# 03_-_MCU.net
KiCad netlist of a schematic drawn in Altium Designer
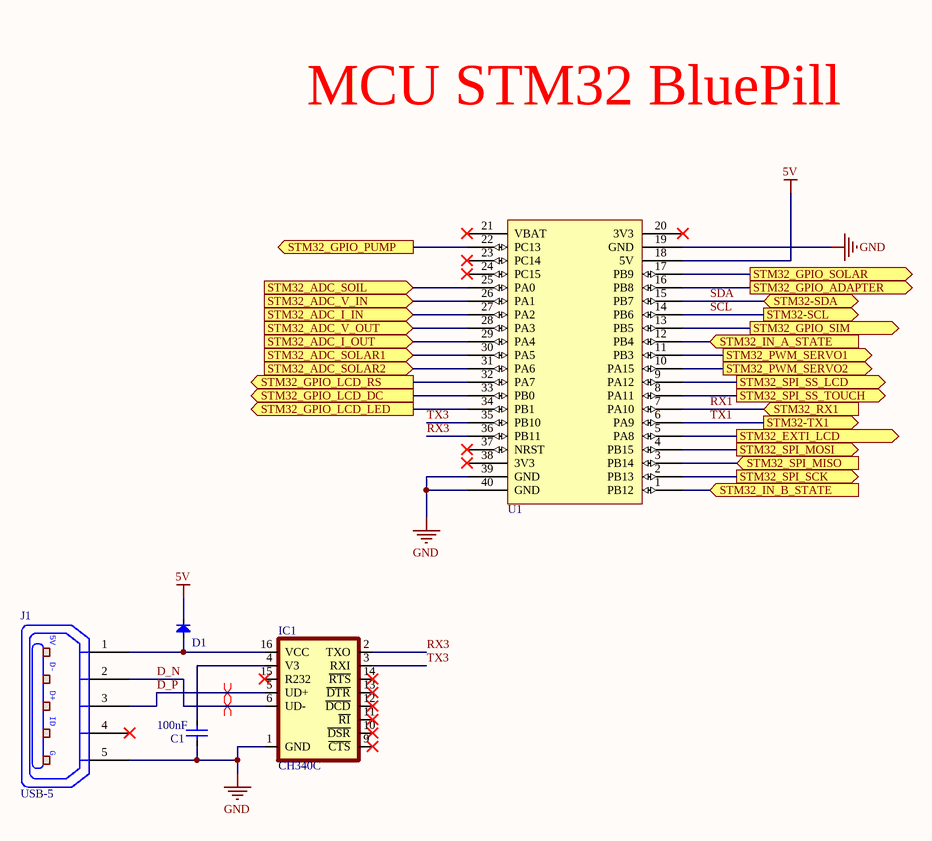
[diagram p0: [03] - MCU.SchDoc]

(export (version "E")
  (design (tool "Eeschema 10.0.6"))
  (components
    (comp (ref "C1")
      (value "100nF")
      (footprint "CAP_0805")
      (description "Capacitor")
      (fields (field (name "PUBLISHER") "Altium Limited"))
      (libsource (lib "My Library") (part "CapSMD"))
    )
    (comp (ref "D1")
      (value "SS34")
      (footprint "DO-214AC(SMA)")
      (description "Diode Schottky 1N5822 3A 40V SMA")
      (fields (field (name "PUBLISHER") "Altium Limited"))
      (libsource (lib "My Library") (part "Diode SMD"))
    )
    (comp (ref "IC1")
      (value "CH340C")
      (footprint "SO016")
      (description "USB to serial chip CH340")
      (fields (field (name "MF") "WCH"))
      (libsource (lib "My Library") (part "CH340C"))
    )
    (comp (ref "J1")
      (value "USB-5")
      (footprint "USB-M1")
      (fields
        (field (name "MANUFACTURER") "FCI")
        (field (name "MANUFACTURER PART NUMBER") "10118193-0001LF")
        (field (name ".CREATOR") "MM")
        (field (name ".CHECKED PCB") "RF")
        (field (name ".CHECKED SCH") "MM")
      )
      (libsource (lib "My Library") (part "USB-5"))
    )
    (comp (ref "U1")
      (value "STM32 BluePill")
      (footprint "STM32 Bluepill")
      (libsource (lib "My Library") (part "STM32 BluePill"))
    )
  )
  (nets
    (net (code "1") (name "/D_N") (class "Default")
      (node (ref "IC1") (pin "6") (pinfunction "UD-_6") (pintype "bidirectional"))
      (node (ref "J1") (pin "2") (pinfunction "P2_2") (pintype "passive"))
    )
    (net (code "2") (name "/D_P") (class "Default")
      (node (ref "IC1") (pin "5") (pinfunction "UD+_5") (pintype "bidirectional"))
      (node (ref "J1") (pin "3") (pinfunction "P3_3") (pintype "passive"))
    )
    (net (code "3") (name "/RX1") (class "Default")
      (node (ref "U1") (pin "7") (pinfunction "PA10_7") (pintype "bidirectional"))
    )
    (net (code "4") (name "/RX3") (class "Default")
      (node (ref "IC1") (pin "2") (pinfunction "TXO_2") (pintype "bidirectional"))
      (node (ref "U1") (pin "36") (pinfunction "PB11_36") (pintype "bidirectional"))
    )
    (net (code "5") (name "/SCL") (class "Default")
      (node (ref "U1") (pin "14") (pinfunction "PB6_14") (pintype "bidirectional"))
    )
    (net (code "6") (name "/SDA") (class "Default")
      (node (ref "U1") (pin "15") (pinfunction "PB7_15") (pintype "bidirectional"))
    )
    (net (code "7") (name "/STM32_ADC_I_IN") (class "Default")
      (node (ref "U1") (pin "27") (pinfunction "PA2_27") (pintype "bidirectional"))
    )
    (net (code "8") (name "/STM32_ADC_I_OUT") (class "Default")
      (node (ref "U1") (pin "29") (pinfunction "PA4_29") (pintype "bidirectional"))
    )
    (net (code "9") (name "/STM32_ADC_SOIL") (class "Default")
      (node (ref "U1") (pin "25") (pinfunction "PA0_25") (pintype "bidirectional"))
    )
    (net (code "10") (name "/STM32_ADC_SOLAR1") (class "Default")
      (node (ref "U1") (pin "30") (pinfunction "PA5_30") (pintype "bidirectional"))
    )
    (net (code "11") (name "/STM32_ADC_SOLAR2") (class "Default")
      (node (ref "U1") (pin "31") (pinfunction "PA6_31") (pintype "bidirectional"))
    )
    (net (code "12") (name "/STM32_ADC_V_IN") (class "Default")
      (node (ref "U1") (pin "26") (pinfunction "PA1_26") (pintype "bidirectional"))
    )
    (net (code "13") (name "/STM32_ADC_V_OUT") (class "Default")
      (node (ref "U1") (pin "28") (pinfunction "PA3_28") (pintype "bidirectional"))
    )
    (net (code "14") (name "/STM32_EXTI_LCD") (class "Default")
      (node (ref "U1") (pin "5") (pinfunction "PA8_5") (pintype "bidirectional"))
    )
    (net (code "15") (name "/STM32_GPIO_ADAPTER") (class "Default")
      (node (ref "U1") (pin "16") (pinfunction "PB8_16") (pintype "bidirectional"))
    )
    (net (code "16") (name "/STM32_GPIO_LCD_DC") (class "Default")
      (node (ref "U1") (pin "33") (pinfunction "PB0_33") (pintype "bidirectional"))
    )
    (net (code "17") (name "/STM32_GPIO_LCD_LED") (class "Default")
      (node (ref "U1") (pin "34") (pinfunction "PB1_34") (pintype "bidirectional"))
    )
    (net (code "18") (name "/STM32_GPIO_LCD_RS") (class "Default")
      (node (ref "U1") (pin "32") (pinfunction "PA7_32") (pintype "bidirectional"))
    )
    (net (code "19") (name "/STM32_GPIO_PUMP") (class "Default")
      (node (ref "U1") (pin "22") (pinfunction "PC13_22") (pintype "bidirectional"))
    )
    (net (code "20") (name "/STM32_GPIO_SIM") (class "Default")
      (node (ref "U1") (pin "13") (pinfunction "PB5_13") (pintype "bidirectional"))
    )
    (net (code "21") (name "/STM32_GPIO_SOLAR") (class "Default")
      (node (ref "U1") (pin "17") (pinfunction "PB9_17") (pintype "bidirectional"))
    )
    (net (code "22") (name "/STM32_IN_A_STATE") (class "Default")
      (node (ref "U1") (pin "12") (pinfunction "PB4_12") (pintype "bidirectional"))
    )
    (net (code "23") (name "/STM32_IN_B_STATE") (class "Default")
      (node (ref "U1") (pin "1") (pinfunction "PB12_1") (pintype "bidirectional"))
    )
    (net (code "24") (name "/STM32_PWM_SERVO1") (class "Default")
      (node (ref "U1") (pin "11") (pinfunction "PB3_11") (pintype "bidirectional"))
    )
    (net (code "25") (name "/STM32_PWM_SERVO2") (class "Default")
      (node (ref "U1") (pin "10") (pinfunction "PA15_10") (pintype "bidirectional"))
    )
    (net (code "26") (name "/STM32_SPI_MISO") (class "Default")
      (node (ref "U1") (pin "3") (pinfunction "PB14_3") (pintype "bidirectional"))
    )
    (net (code "27") (name "/STM32_SPI_MOSI") (class "Default")
      (node (ref "U1") (pin "4") (pinfunction "PB15_4") (pintype "bidirectional"))
    )
    (net (code "28") (name "/STM32_SPI_SCK") (class "Default")
      (node (ref "U1") (pin "2") (pinfunction "PB13_2") (pintype "bidirectional"))
    )
    (net (code "29") (name "/STM32_SPI_SS_LCD") (class "Default")
      (node (ref "U1") (pin "9") (pinfunction "PA12_9") (pintype "bidirectional"))
    )
    (net (code "30") (name "/STM32_SPI_SS_TOUCH") (class "Default")
      (node (ref "U1") (pin "8") (pinfunction "PA11_8") (pintype "bidirectional"))
    )
    (net (code "31") (name "/TX1") (class "Default")
      (node (ref "U1") (pin "6") (pinfunction "PA9_6") (pintype "bidirectional"))
    )
    (net (code "32") (name "/TX3") (class "Default")
      (node (ref "IC1") (pin "3") (pinfunction "RXI_3") (pintype "bidirectional"))
      (node (ref "U1") (pin "35") (pinfunction "PB10_35") (pintype "bidirectional"))
    )
    (net (code "33") (name "5V") (class "Default")
      (node (ref "D1") (pin "2") (pinfunction "K_2") (pintype "passive"))
      (node (ref "U1") (pin "18") (pinfunction "5V_18") (pintype "power_in"))
    )
    (net (code "34") (name "GND") (class "Default")
      (node (ref "C1") (pin "1") (pinfunction "1_1") (pintype "passive"))
      (node (ref "IC1") (pin "1") (pinfunction "GND_1") (pintype "bidirectional"))
      (node (ref "J1") (pin "5") (pinfunction "P5_5") (pintype "passive"))
      (node (ref "U1") (pin "19") (pinfunction "GND_19") (pintype "power_in"))
      (node (ref "U1") (pin "39") (pinfunction "GND_39") (pintype "power_in"))
      (node (ref "U1") (pin "40") (pinfunction "GND_40") (pintype "power_in"))
    )
    (net (code "35") (name "Net-(D1-A)") (class "Default")
      (node (ref "D1") (pin "1") (pinfunction "A_1") (pintype "passive"))
      (node (ref "IC1") (pin "16") (pinfunction "VCC_16") (pintype "bidirectional"))
      (node (ref "J1") (pin "1") (pinfunction "P1_1") (pintype "passive"))
    )
    (net (code "36") (name "Net-(IC1-V3)") (class "Default")
      (node (ref "C1") (pin "2") (pinfunction "2_2") (pintype "passive"))
      (node (ref "IC1") (pin "4") (pinfunction "V3_4") (pintype "bidirectional"))
    )
    (net (code "37") (name "unconnected-(IC1-R232-Pad15)") (class "Default")
      (node (ref "IC1") (pin "15") (pinfunction "R232_15") (pintype "bidirectional+no_connect"))
    )
    (net (code "38") (name "unconnected-(IC1-~{CTS}-Pad9)") (class "Default")
      (node (ref "IC1") (pin "9") (pinfunction "~{CTS}_9") (pintype "bidirectional+no_connect"))
    )
    (net (code "39") (name "unconnected-(IC1-~{DCD}-Pad12)") (class "Default")
      (node (ref "IC1") (pin "12") (pinfunction "~{DCD}_12") (pintype "bidirectional+no_connect"))
    )
    (net (code "40") (name "unconnected-(IC1-~{DSR}-Pad10)") (class "Default")
      (node (ref "IC1") (pin "10") (pinfunction "~{DSR}_10") (pintype "bidirectional+no_connect"))
    )
    (net (code "41") (name "unconnected-(IC1-~{DTR}-Pad13)") (class "Default")
      (node (ref "IC1") (pin "13") (pinfunction "~{DTR}_13") (pintype "bidirectional+no_connect"))
    )
    (net (code "42") (name "unconnected-(IC1-~{RI}-Pad11)") (class "Default")
      (node (ref "IC1") (pin "11") (pinfunction "~{RI}_11") (pintype "bidirectional+no_connect"))
    )
    (net (code "43") (name "unconnected-(IC1-~{RTS}-Pad14)") (class "Default")
      (node (ref "IC1") (pin "14") (pinfunction "~{RTS}_14") (pintype "bidirectional+no_connect"))
    )
    (net (code "44") (name "unconnected-(J1-P4-Pad4)") (class "Default")
      (node (ref "J1") (pin "4") (pinfunction "P4_4") (pintype "passive+no_connect"))
    )
    (net (code "45") (name "unconnected-(U1-3V3-Pad20)") (class "Default")
      (node (ref "U1") (pin "20") (pinfunction "3V3_20") (pintype "power_in+no_connect"))
    )
    (net (code "46") (name "unconnected-(U1-3V3-Pad38)") (class "Default")
      (node (ref "U1") (pin "38") (pinfunction "3V3_38") (pintype "power_in+no_connect"))
    )
    (net (code "47") (name "unconnected-(U1-NRST-Pad37)") (class "Default")
      (node (ref "U1") (pin "37") (pinfunction "NRST_37") (pintype "bidirectional+no_connect"))
    )
    (net (code "48") (name "unconnected-(U1-PC14-Pad23)") (class "Default")
      (node (ref "U1") (pin "23") (pinfunction "PC14_23") (pintype "bidirectional+no_connect"))
    )
    (net (code "49") (name "unconnected-(U1-PC15-Pad24)") (class "Default")
      (node (ref "U1") (pin "24") (pinfunction "PC15_24") (pintype "bidirectional+no_connect"))
    )
    (net (code "50") (name "unconnected-(U1-VBAT-Pad21)") (class "Default")
      (node (ref "U1") (pin "21") (pinfunction "VBAT_21") (pintype "power_in+no_connect"))
    )
  )
)
